# S7G7_footprint_simplified_w_ethernet_v1p.net
KiCad netlist of a schematic drawn in EAGLE
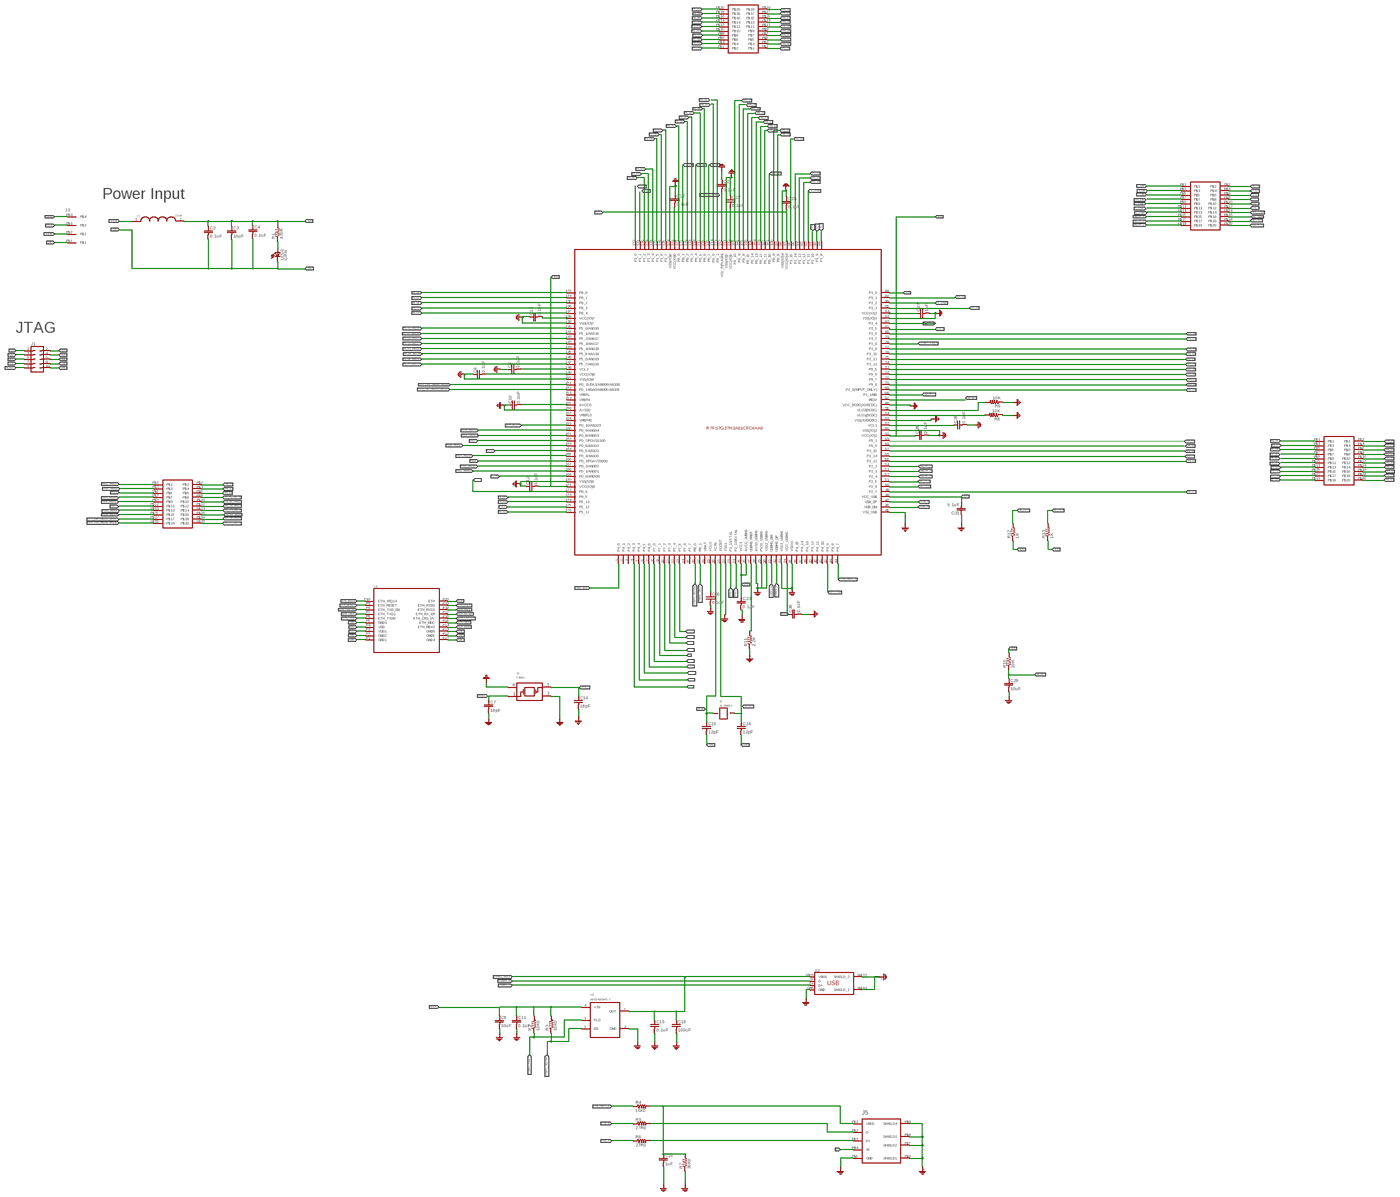
[diagram p0: schematic, sheet 1, overview]
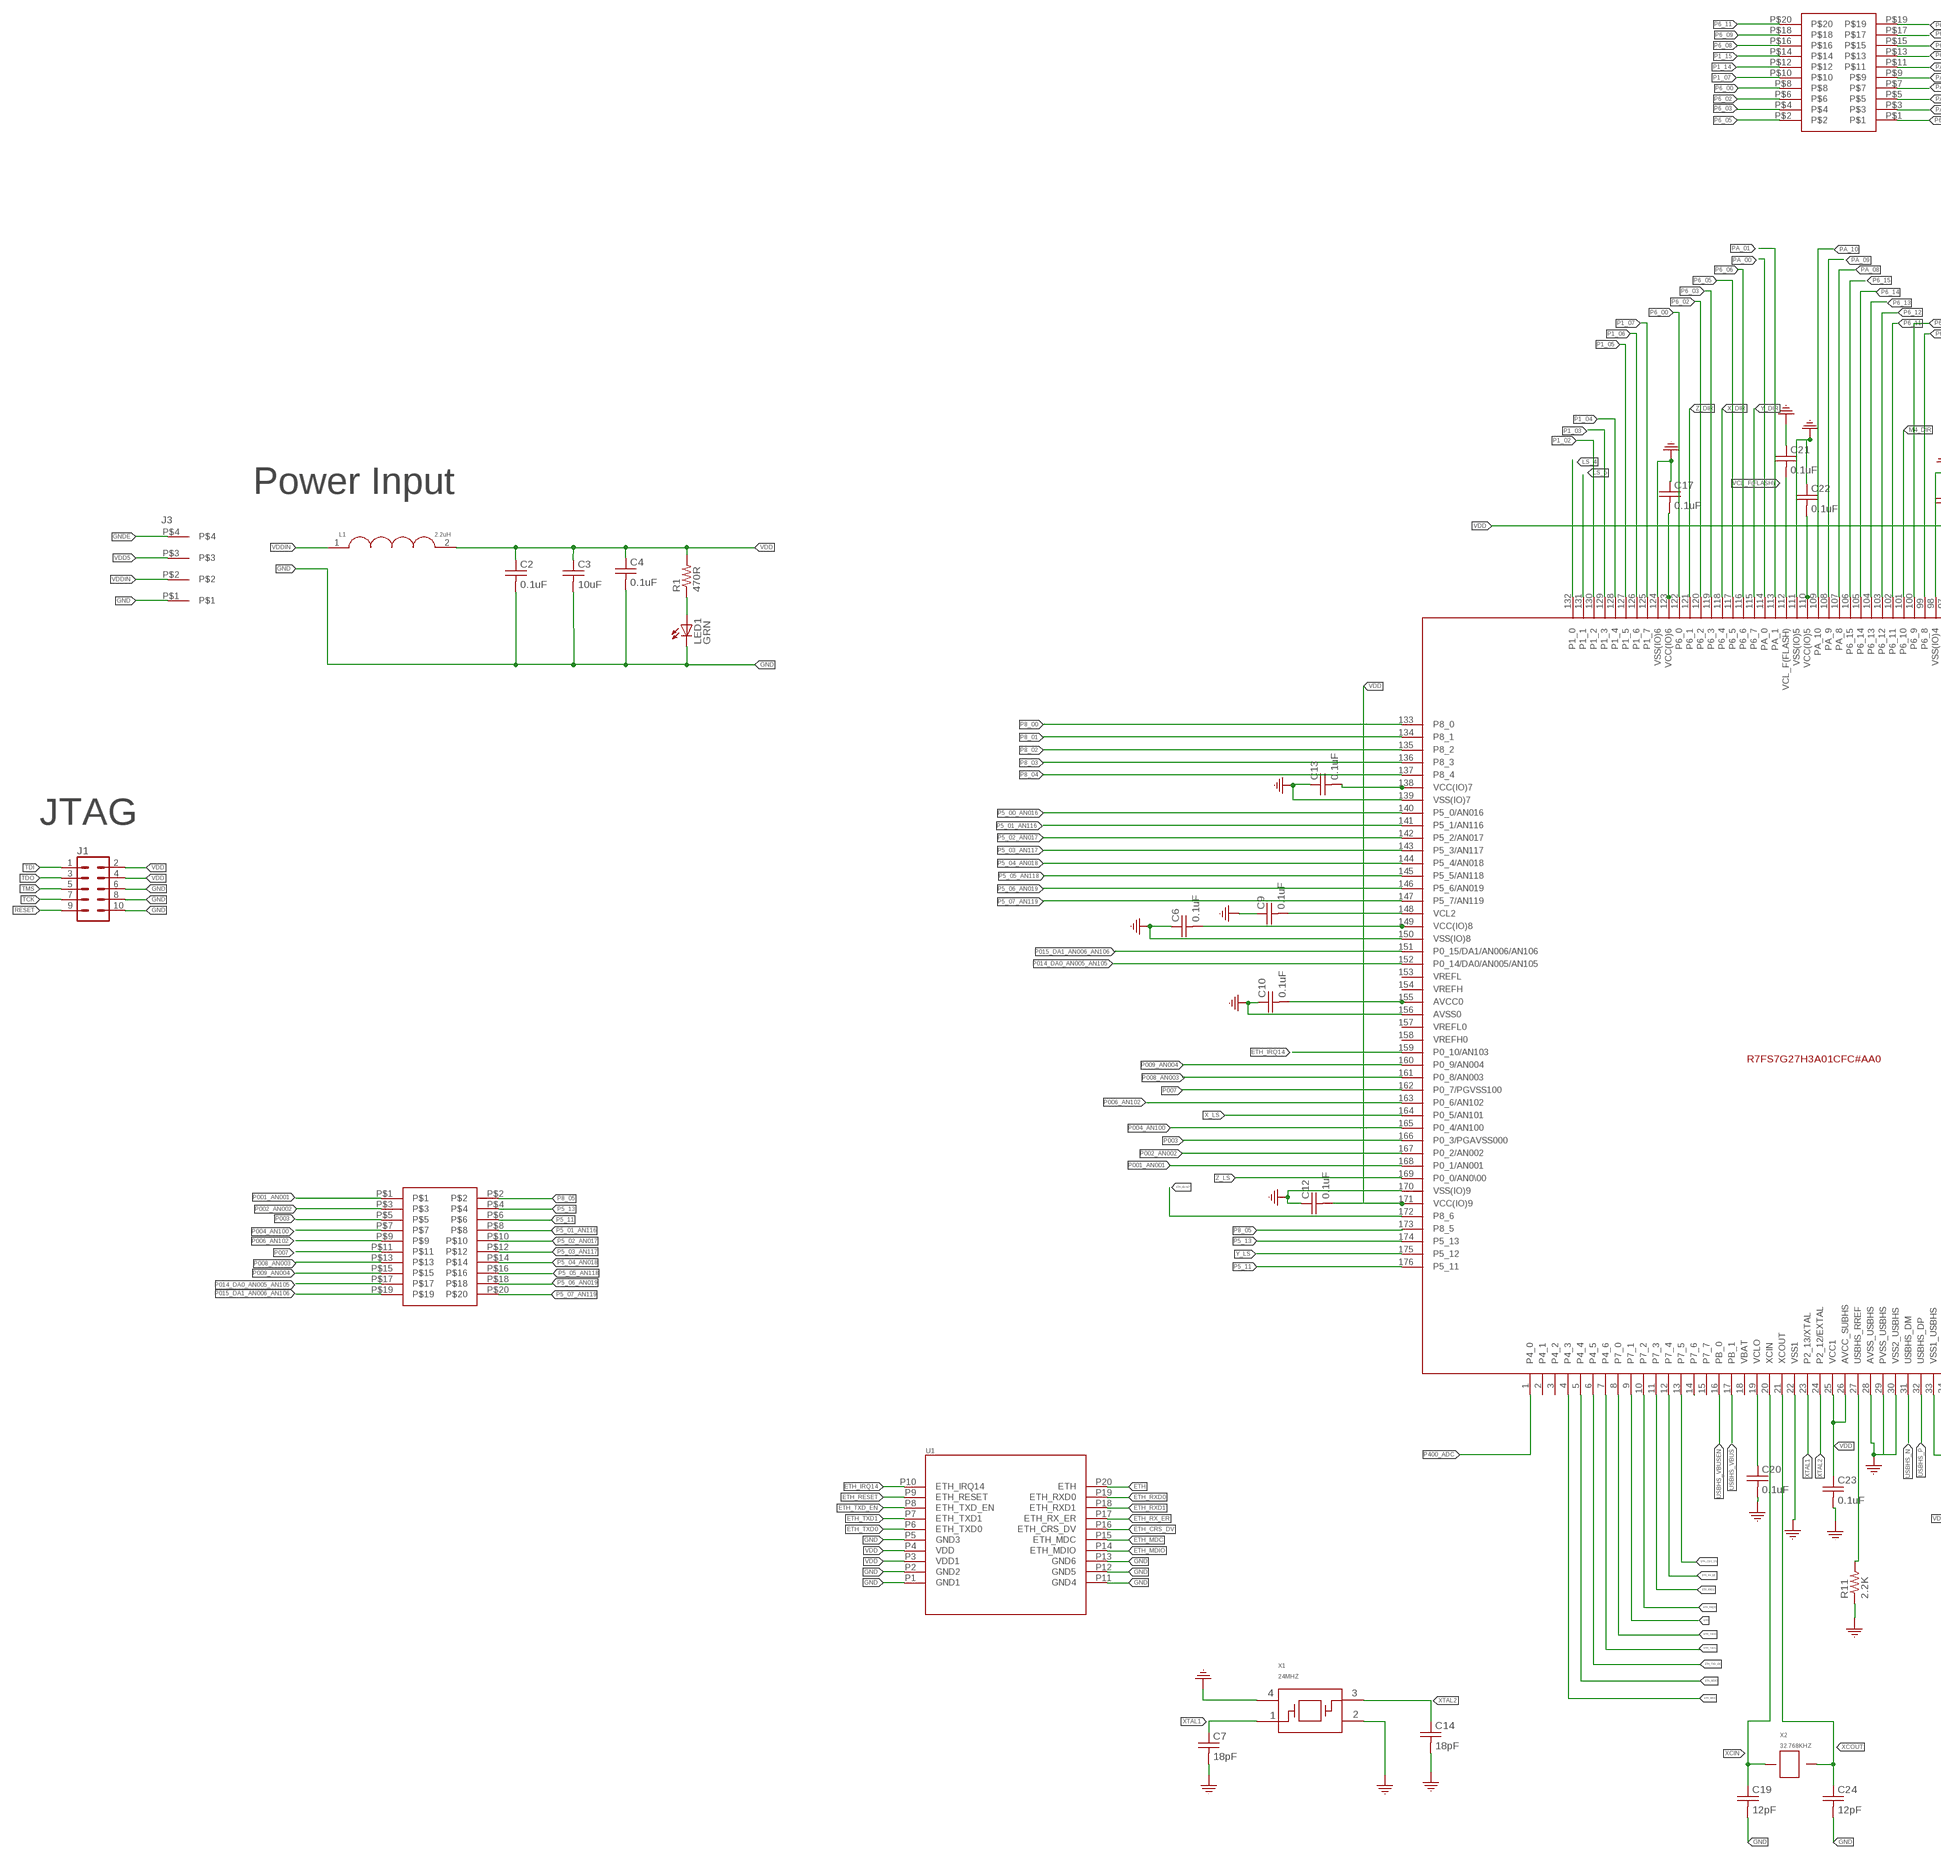
[diagram p1: schematic, sheet 1, part 1 of 4]
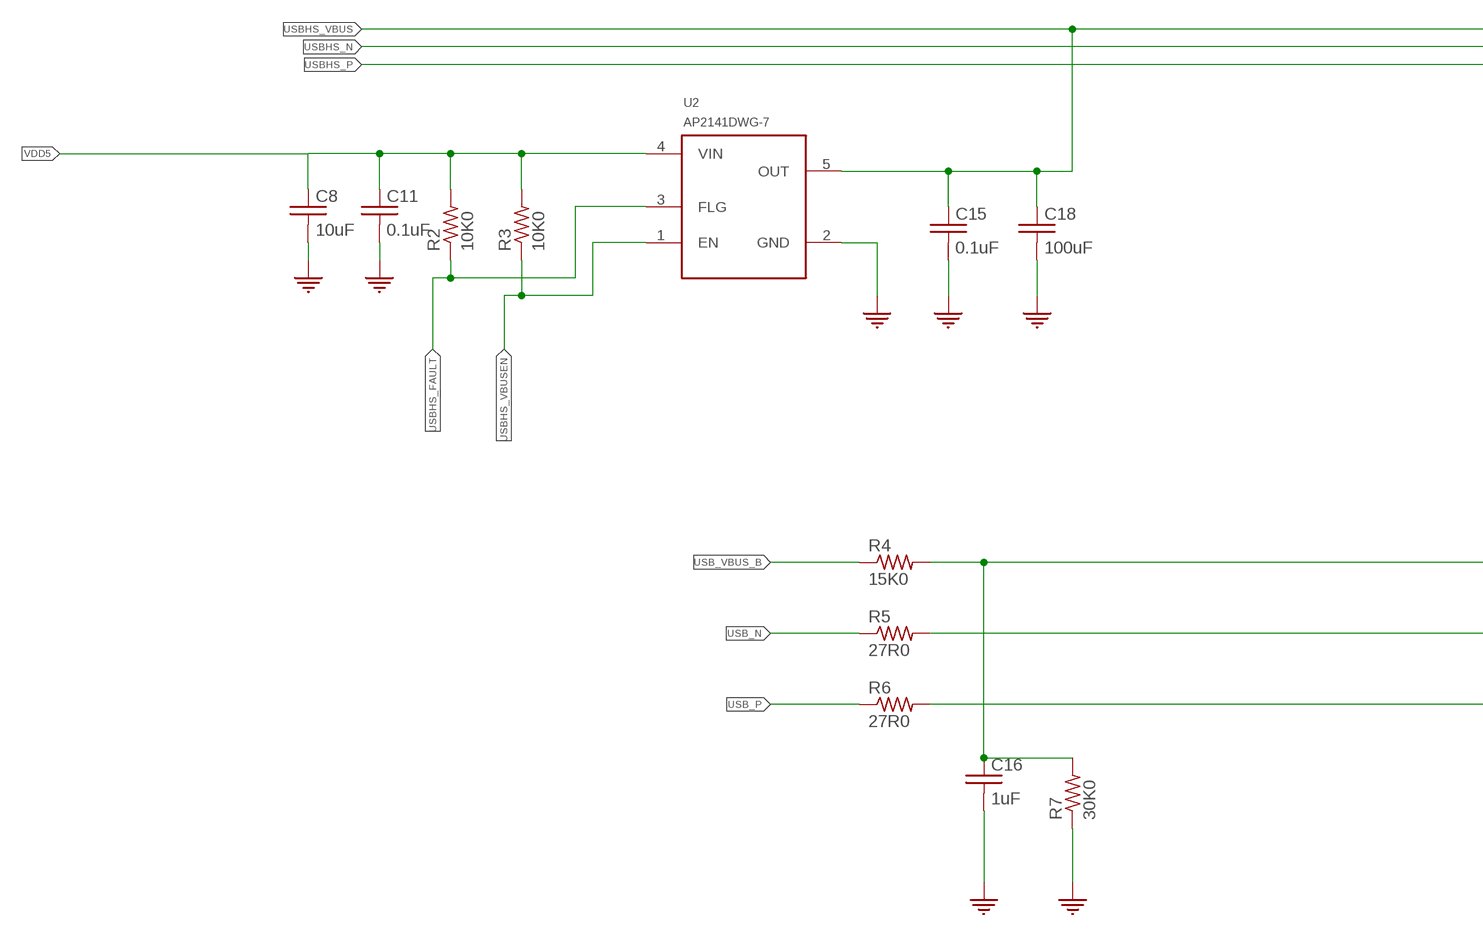
[diagram p2: schematic, sheet 1, part 2 of 4]
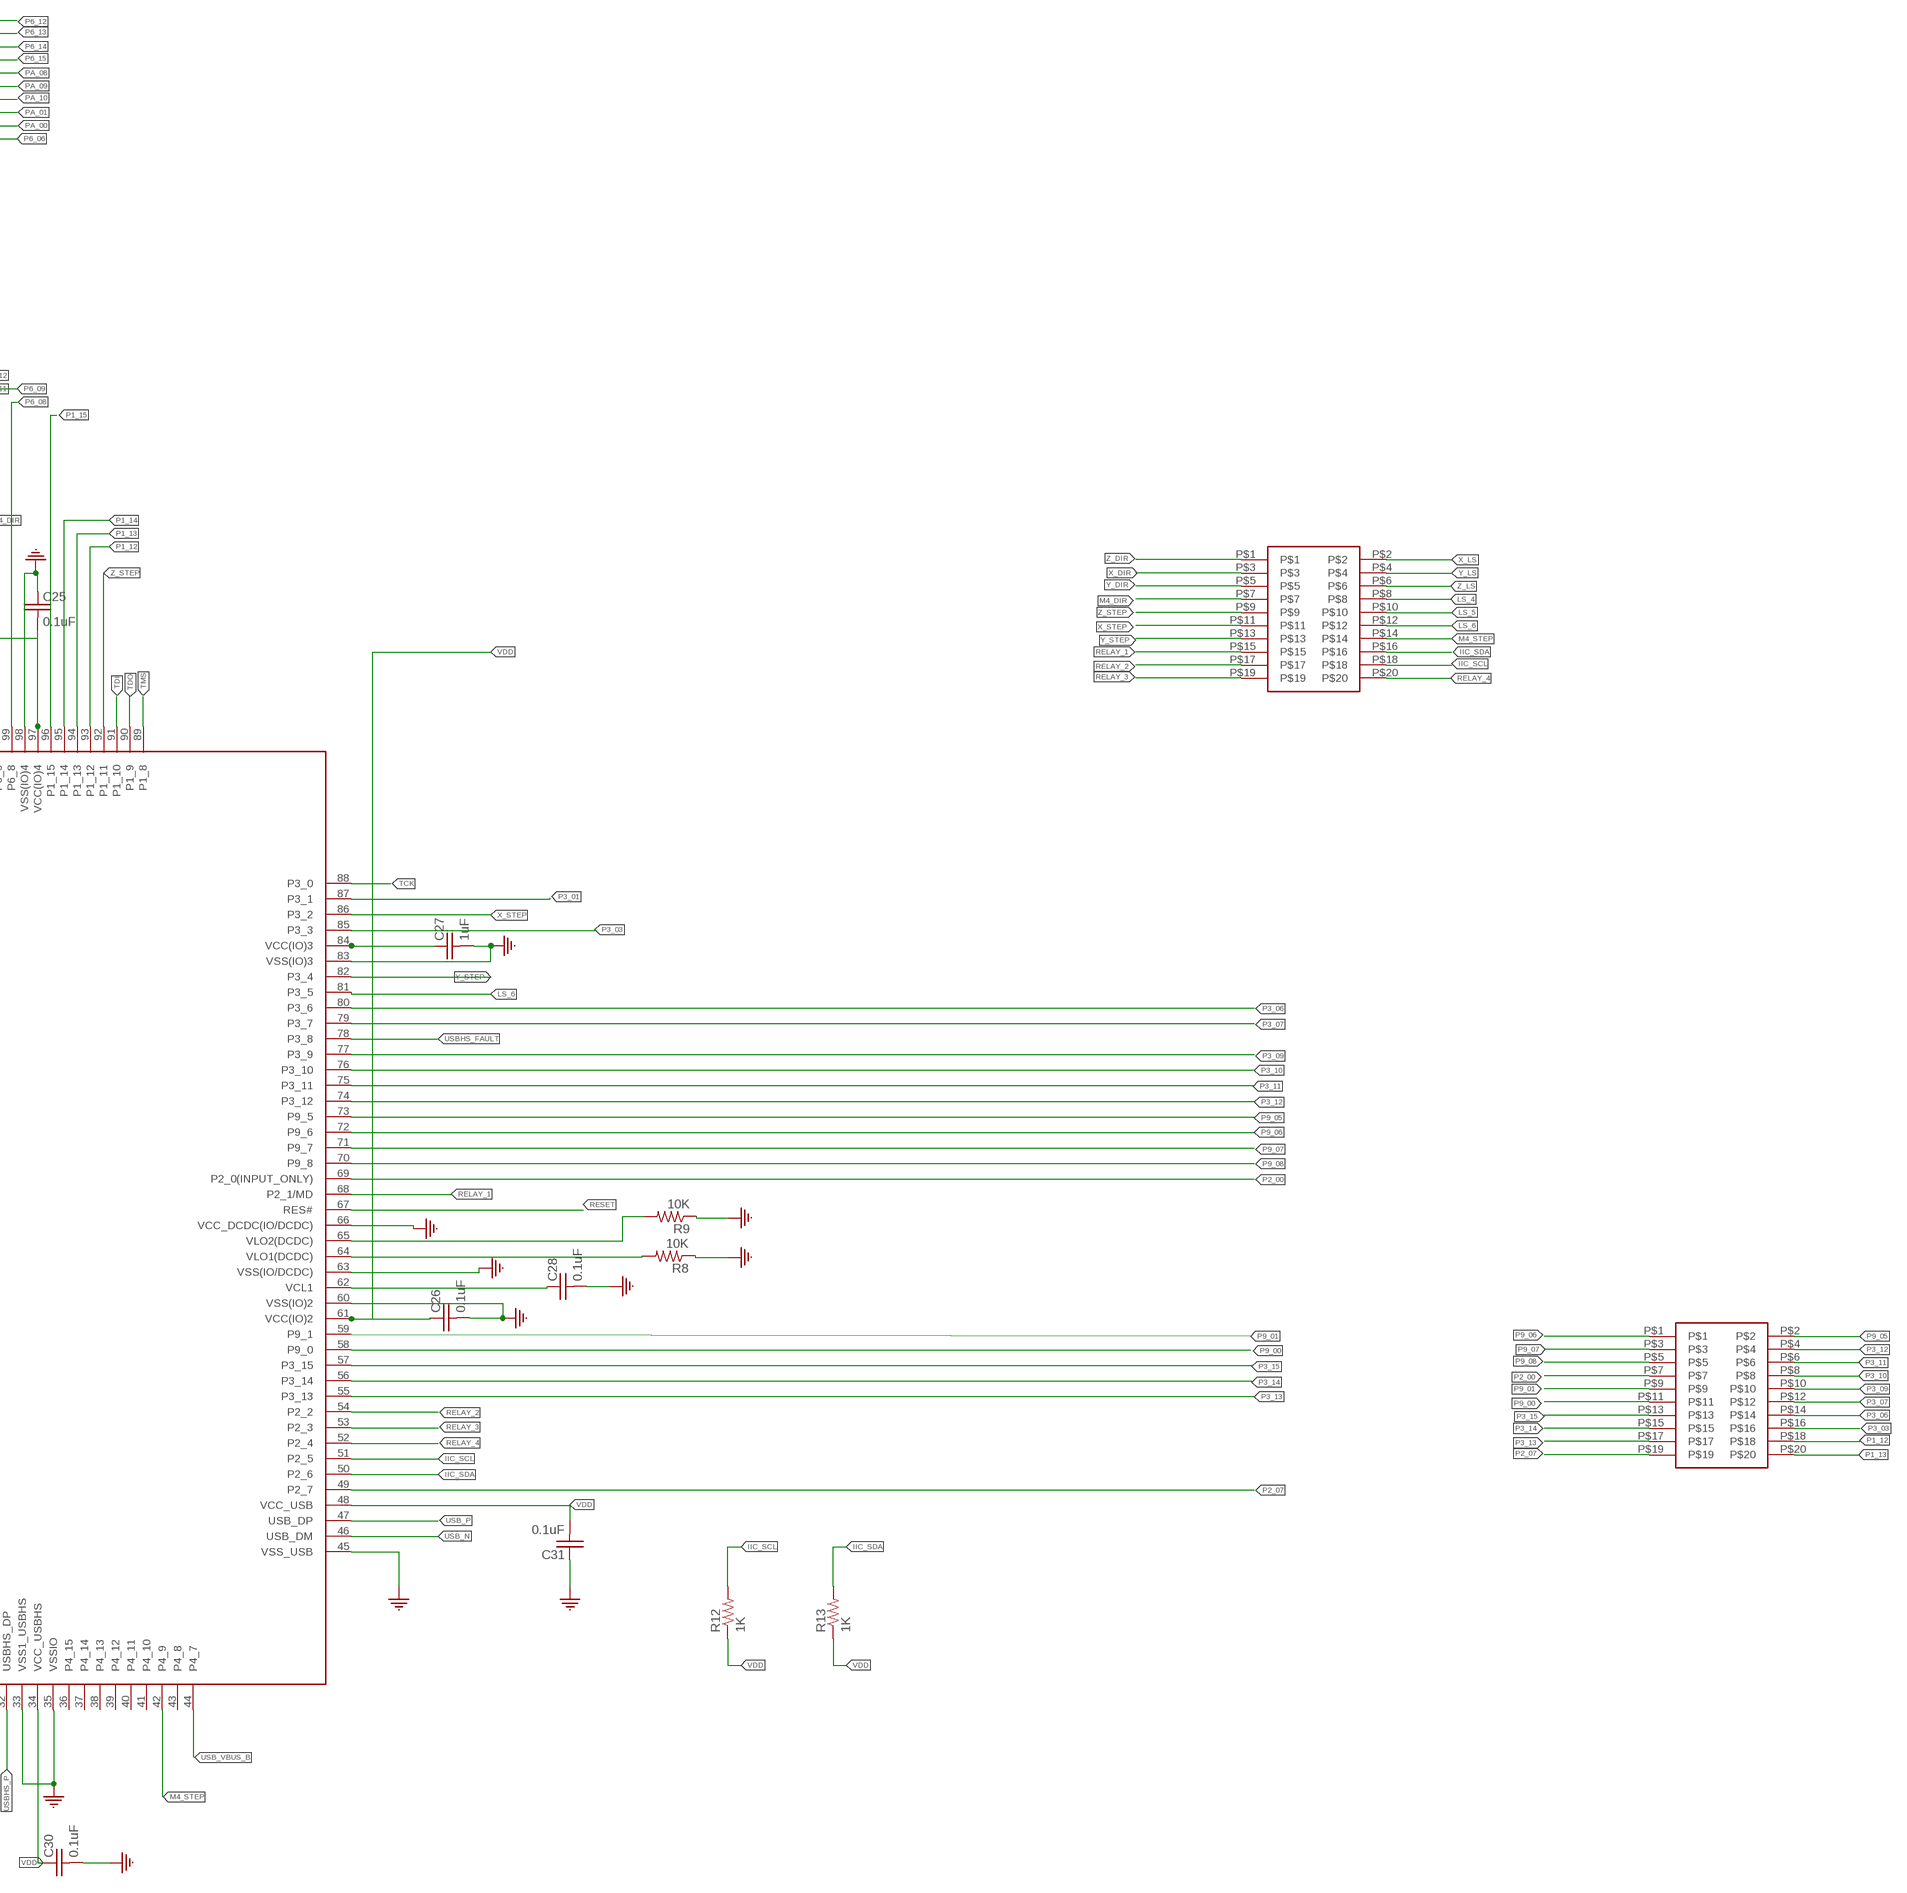
[diagram p3: schematic, sheet 1, part 3 of 4]
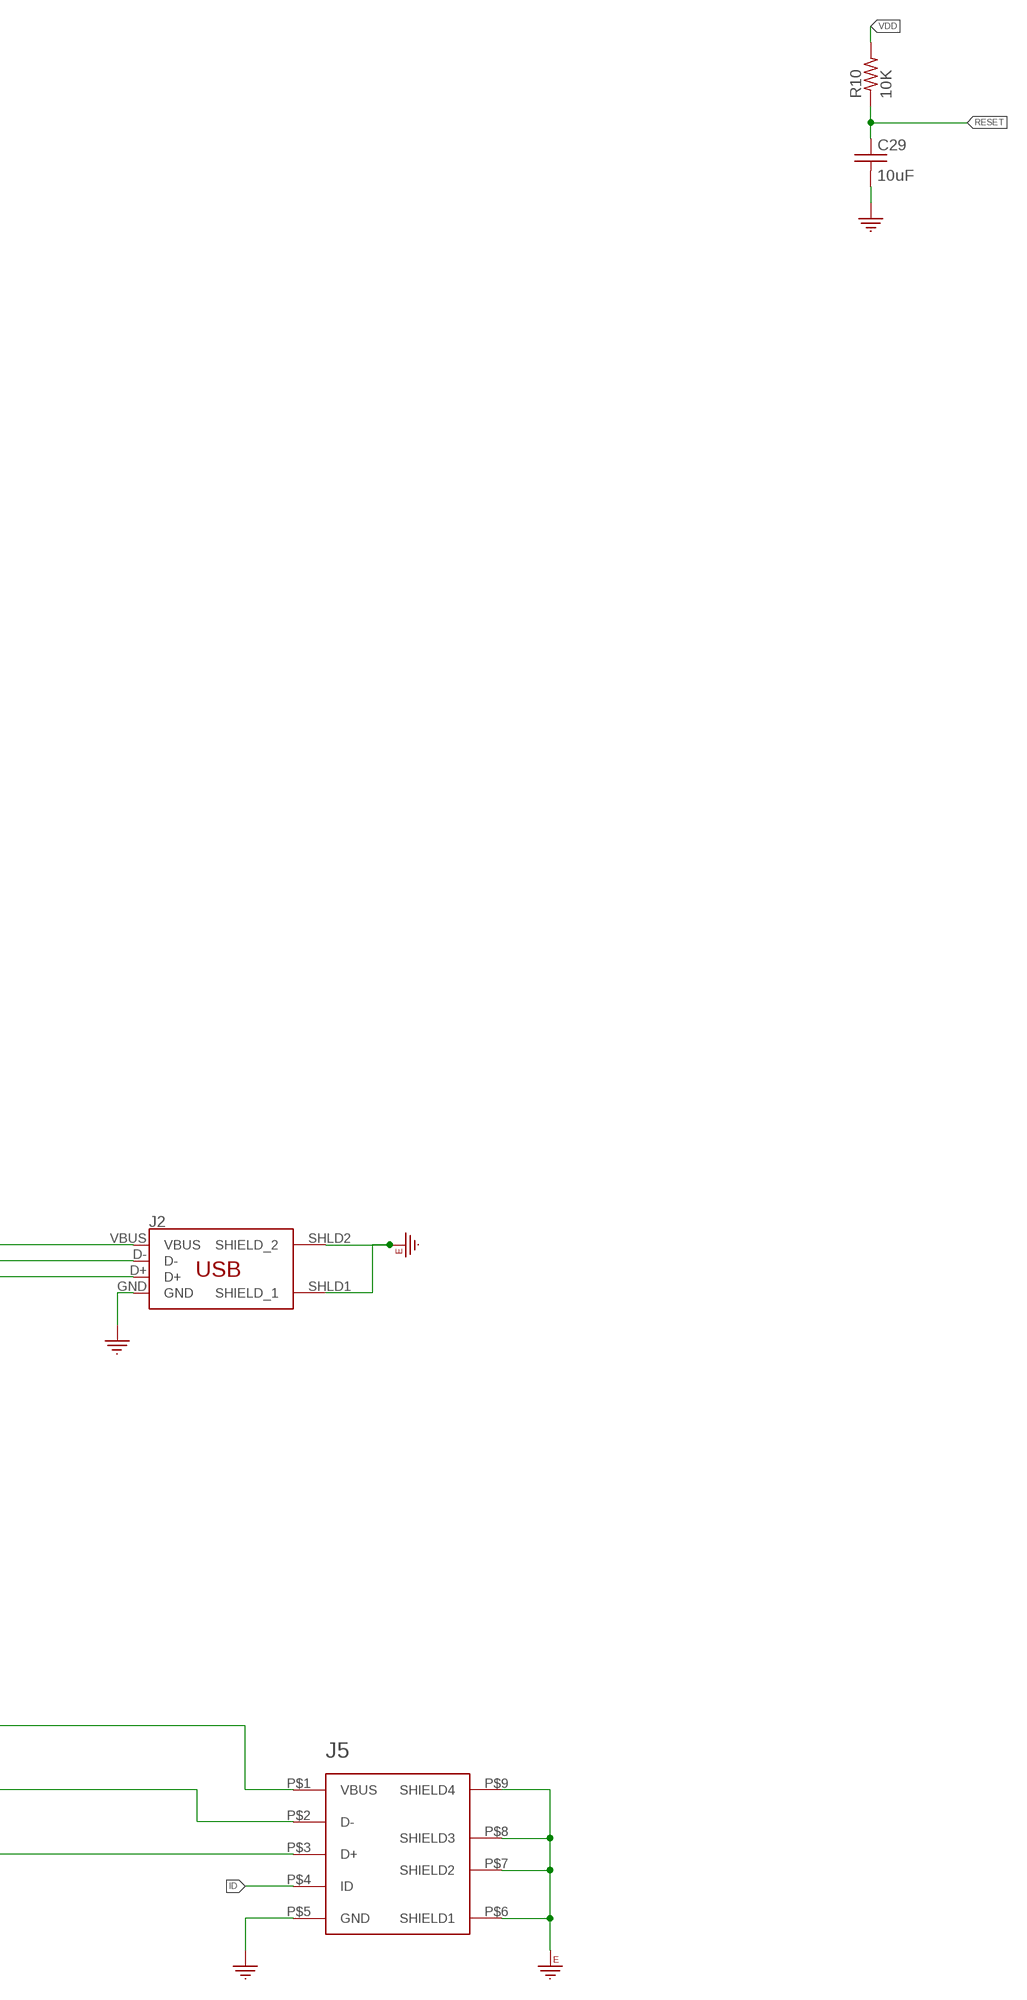
[diagram p4: schematic, sheet 1, part 4 of 4]

(export (version "E")
  (design (tool "Eeschema 10.0.6"))
  (components
    (comp (ref "C2")
      (value "0.1uF")
      (footprint "eagle-import:0402")
      (libsource (lib "eagle-import") (part "C_0402"))
    )
    (comp (ref "C3")
      (value "10uF")
      (footprint "eagle-import:0402")
      (libsource (lib "eagle-import") (part "C_0402"))
    )
    (comp (ref "C4")
      (value "0.1uF")
      (footprint "eagle-import:0402")
      (libsource (lib "eagle-import") (part "C_0402"))
    )
    (comp (ref "C6")
      (value "0.1uF")
      (footprint "eagle-import:0402")
      (libsource (lib "eagle-import") (part "C_0402"))
    )
    (comp (ref "C7")
      (value "18pF")
      (footprint "eagle-import:0402")
      (libsource (lib "eagle-import") (part "C_0402"))
    )
    (comp (ref "C8")
      (value "10uF")
      (footprint "eagle-import:0402")
      (libsource (lib "eagle-import") (part "C_0402"))
    )
    (comp (ref "C9")
      (value "0.1uF")
      (footprint "eagle-import:0402")
      (libsource (lib "eagle-import") (part "C_0402"))
    )
    (comp (ref "C10")
      (value "0.1uF")
      (footprint "eagle-import:0402")
      (libsource (lib "eagle-import") (part "C_0402"))
    )
    (comp (ref "C11")
      (value "0.1uF")
      (footprint "eagle-import:0402")
      (libsource (lib "eagle-import") (part "C_0402"))
    )
    (comp (ref "C12")
      (value "0.1uF")
      (footprint "eagle-import:0402")
      (libsource (lib "eagle-import") (part "C_0402"))
    )
    (comp (ref "C13")
      (value "0.1uF")
      (footprint "eagle-import:0402")
      (libsource (lib "eagle-import") (part "C_0402"))
    )
    (comp (ref "C14")
      (value "18pF")
      (footprint "eagle-import:0402")
      (libsource (lib "eagle-import") (part "C_0402"))
    )
    (comp (ref "C15")
      (value "0.1uF")
      (footprint "eagle-import:0402")
      (libsource (lib "eagle-import") (part "C_0402"))
    )
    (comp (ref "C16")
      (value "1uF")
      (footprint "eagle-import:0402")
      (libsource (lib "eagle-import") (part "C_0402"))
    )
    (comp (ref "C17")
      (value "0.1uF")
      (footprint "eagle-import:0402")
      (libsource (lib "eagle-import") (part "C_0402"))
    )
    (comp (ref "C18")
      (value "100uF")
      (footprint "eagle-import:C1210")
      (libsource (lib "eagle-import") (part "C_1210"))
    )
    (comp (ref "C19")
      (value "12pF")
      (footprint "eagle-import:0402")
      (libsource (lib "eagle-import") (part "C_0402"))
    )
    (comp (ref "C20")
      (value "0.1uF")
      (footprint "eagle-import:0402")
      (libsource (lib "eagle-import") (part "C_0402"))
    )
    (comp (ref "C21")
      (value "0.1uF")
      (footprint "eagle-import:0402")
      (libsource (lib "eagle-import") (part "C_0402"))
    )
    (comp (ref "C22")
      (value "0.1uF")
      (footprint "eagle-import:0402")
      (libsource (lib "eagle-import") (part "C_0402"))
    )
    (comp (ref "C23")
      (value "0.1uF")
      (footprint "eagle-import:0402")
      (libsource (lib "eagle-import") (part "C_0402"))
    )
    (comp (ref "C24")
      (value "12pF")
      (footprint "eagle-import:0402")
      (libsource (lib "eagle-import") (part "C_0402"))
    )
    (comp (ref "C25")
      (value "0.1uF")
      (footprint "eagle-import:0402")
      (libsource (lib "eagle-import") (part "C_0402"))
    )
    (comp (ref "C26")
      (value "0.1uF")
      (footprint "eagle-import:0402")
      (libsource (lib "eagle-import") (part "C_0402"))
    )
    (comp (ref "C27")
      (value "1uF")
      (footprint "eagle-import:0402")
      (libsource (lib "eagle-import") (part "C_0402"))
    )
    (comp (ref "C28")
      (value "0.1uF")
      (footprint "eagle-import:0402")
      (libsource (lib "eagle-import") (part "C_0402"))
    )
    (comp (ref "C29")
      (value "10uF")
      (footprint "eagle-import:0402")
      (libsource (lib "eagle-import") (part "C_0402"))
    )
    (comp (ref "C30")
      (value "0.1uF")
      (footprint "eagle-import:0402")
      (libsource (lib "eagle-import") (part "C_0402"))
    )
    (comp (ref "C31")
      (value "0.1uF")
      (footprint "eagle-import:0402")
      (libsource (lib "eagle-import") (part "C_0402"))
    )
    (comp (ref "J1")
      (value "CONN_05X2PTH")
      (footprint "eagle-import:2X5")
      (libsource (lib "eagle-import") (part "CONN_05X2PTH"))
    )
    (comp (ref "J2")
      (value "USB_A")
      (footprint "eagle-import:USB_A_SMT")
      (libsource (lib "eagle-import") (part "USB_A"))
    )
    (comp (ref "J3")
      (value "3.81MM_1_X_4_RT_ANGLE_PLUG_HEADER")
      (footprint "eagle-import:1X4_3.81MM_PITCH")
      (libsource (lib "eagle-import") (part "3.81MM_1_X_4_RT_ANGLE_PLUG_HEADER"))
    )
    (comp (ref "J4")
      (value "2_X_10_HEADER_GENERIC")
      (footprint "eagle-import:2_X_10_.1_INCH")
      (libsource (lib "eagle-import") (part "2_X_10_HEADER_GENERIC"))
    )
    (comp (ref "J5")
      (value "USB_MICRO-B")
      (footprint "eagle-import:USB_MICRO-B")
      (libsource (lib "eagle-import") (part "USB_MICRO-B"))
    )
    (comp (ref "JP1")
      (value "2_X_10_HEADER_GENERIC")
      (footprint "eagle-import:2_X_10_.1_INCH")
      (libsource (lib "eagle-import") (part "2_X_10_HEADER_GENERIC"))
    )
    (comp (ref "JP2")
      (value "2_X_10_HEADER_GENERIC")
      (footprint "eagle-import:2_X_10_.1_INCH")
      (libsource (lib "eagle-import") (part "2_X_10_HEADER_GENERIC"))
    )
    (comp (ref "JP3")
      (value "2_X_10_HEADER_GENERIC")
      (footprint "eagle-import:2_X_10_.1_INCH")
      (libsource (lib "eagle-import") (part "2_X_10_HEADER_GENERIC"))
    )
    (comp (ref "L1")
      (value "2.2uH")
      (footprint "eagle-import:1008_(2520_METRIC)")
      (libsource (lib "eagle-import") (part "INDUCTOR_1008_2.2_MH_1.3A"))
    )
    (comp (ref "LED1")
      (value "LED_0805_GREEN")
      (footprint "eagle-import:LED_0805_GREEN")
      (libsource (lib "eagle-import") (part "LED_0805_GREEN"))
    )
    (comp (ref "R1")
      (value "470R")
      (footprint "eagle-import:0402")
      (libsource (lib "eagle-import") (part "R_0402"))
    )
    (comp (ref "R2")
      (value "10K0")
      (footprint "eagle-import:0402")
      (libsource (lib "eagle-import") (part "R_0402"))
    )
    (comp (ref "R3")
      (value "10K0")
      (footprint "eagle-import:0402")
      (libsource (lib "eagle-import") (part "R_0402"))
    )
    (comp (ref "R4")
      (value "15K0")
      (footprint "eagle-import:0402")
      (libsource (lib "eagle-import") (part "R_0402"))
    )
    (comp (ref "R5")
      (value "27R0")
      (footprint "eagle-import:0402")
      (libsource (lib "eagle-import") (part "R_0402"))
    )
    (comp (ref "R6")
      (value "27R0")
      (footprint "eagle-import:0402")
      (libsource (lib "eagle-import") (part "R_0402"))
    )
    (comp (ref "R7")
      (value "30K0")
      (footprint "eagle-import:0402")
      (libsource (lib "eagle-import") (part "R_0402"))
    )
    (comp (ref "R8")
      (value "10K")
      (footprint "eagle-import:0402")
      (libsource (lib "eagle-import") (part "R_0402"))
    )
    (comp (ref "R9")
      (value "10K")
      (footprint "eagle-import:0402")
      (libsource (lib "eagle-import") (part "R_0402"))
    )
    (comp (ref "R10")
      (value "10K")
      (footprint "eagle-import:0402")
      (libsource (lib "eagle-import") (part "R_0402"))
    )
    (comp (ref "R11")
      (value "2.2K")
      (footprint "eagle-import:0402")
      (libsource (lib "eagle-import") (part "R_0402"))
    )
    (comp (ref "R12")
      (value "1K")
      (footprint "eagle-import:0402")
      (libsource (lib "eagle-import") (part "R_0402"))
    )
    (comp (ref "R13")
      (value "1K")
      (footprint "eagle-import:0402")
      (libsource (lib "eagle-import") (part "R_0402"))
    )
    (comp (ref "U1")
      (value "ETHERNET_HAT")
      (footprint "eagle-import:ETHERNET_HAT")
      (libsource (lib "eagle-import") (part "ETHERNET_HAT"))
    )
    (comp (ref "U2")
      (value "AP2141DWG-5")
      (footprint "eagle-import:SOT-23-5")
      (libsource (lib "eagle-import") (part "AP2141DWG-5"))
    )
    (comp (ref "U5")
      (value "S7G2_X_176")
      (footprint "eagle-import:LQFP176_24X24")
      (libsource (lib "eagle-import") (part "S7G2_X_176"))
    )
    (comp (ref "X1")
      (value "24MHZ")
      (footprint "eagle-import:SMD_3225")
      (libsource (lib "eagle-import") (part "XTAL_24_MHZ"))
    )
    (comp (ref "X2")
      (value "32.768KHZ")
      (footprint "eagle-import:SMD_X_2_PADS")
      (libsource (lib "eagle-import") (part "XTAL_32.768KHZ"))
    )
  )
  (nets
    (net (code "1") (name "ETH") (class "Default")
      (node (ref "U1") (pin "P20") (pinfunction "ETH_P20") (pintype "bidirectional"))
      (node (ref "U5") (pin "9") (pinfunction "P7_1_9") (pintype "bidirectional"))
    )
    (net (code "2") (name "ETH_CRS_DV") (class "Default")
      (node (ref "U1") (pin "P16") (pinfunction "ETH_CRS_DV_P16") (pintype "bidirectional"))
      (node (ref "U5") (pin "13") (pinfunction "P7_5_13") (pintype "bidirectional"))
    )
    (net (code "3") (name "ETH_IRQ14") (class "Default")
      (node (ref "U1") (pin "P10") (pinfunction "ETH_IRQ14_P10") (pintype "bidirectional"))
      (node (ref "U5") (pin "159") (pinfunction "P0_10/AN103_159") (pintype "bidirectional"))
    )
    (net (code "4") (name "ETH_MDC") (class "Default")
      (node (ref "U1") (pin "P15") (pinfunction "ETH_MDC_P15") (pintype "bidirectional"))
      (node (ref "U5") (pin "4") (pinfunction "P4_3_4") (pintype "bidirectional"))
    )
    (net (code "5") (name "ETH_MDIO") (class "Default")
      (node (ref "U1") (pin "P14") (pinfunction "ETH_MDIO_P14") (pintype "bidirectional"))
      (node (ref "U5") (pin "5") (pinfunction "P4_4_5") (pintype "bidirectional"))
    )
    (net (code "6") (name "ETH_RESET") (class "Default")
      (node (ref "U1") (pin "P9") (pinfunction "ETH_RESET_P9") (pintype "bidirectional"))
      (node (ref "U5") (pin "172") (pinfunction "P8_6_172") (pintype "bidirectional"))
    )
    (net (code "7") (name "ETH_RXD0") (class "Default")
      (node (ref "U1") (pin "P19") (pinfunction "ETH_RXD0_P19") (pintype "bidirectional"))
      (node (ref "U5") (pin "10") (pinfunction "P7_2_10") (pintype "bidirectional"))
    )
    (net (code "8") (name "ETH_RXD1") (class "Default")
      (node (ref "U1") (pin "P18") (pinfunction "ETH_RXD1_P18") (pintype "bidirectional"))
      (node (ref "U5") (pin "11") (pinfunction "P7_3_11") (pintype "bidirectional"))
    )
    (net (code "9") (name "ETH_RX_ER") (class "Default")
      (node (ref "U1") (pin "P17") (pinfunction "ETH_RX_ER_P17") (pintype "bidirectional"))
      (node (ref "U5") (pin "12") (pinfunction "P7_4_12") (pintype "bidirectional"))
    )
    (net (code "10") (name "ETH_TXD0") (class "Default")
      (node (ref "U1") (pin "P6") (pinfunction "ETH_TXD0_P6") (pintype "bidirectional"))
      (node (ref "U5") (pin "8") (pinfunction "P7_0_8") (pintype "bidirectional"))
    )
    (net (code "11") (name "ETH_TXD1") (class "Default")
      (node (ref "U1") (pin "P7") (pinfunction "ETH_TXD1_P7") (pintype "bidirectional"))
      (node (ref "U5") (pin "7") (pinfunction "P4_6_7") (pintype "bidirectional"))
    )
    (net (code "12") (name "ETH_TXD_EN") (class "Default")
      (node (ref "U1") (pin "P8") (pinfunction "ETH_TXD_EN_P8") (pintype "bidirectional"))
      (node (ref "U5") (pin "6") (pinfunction "P4_5_6") (pintype "bidirectional"))
    )
    (net (code "13") (name "GND") (class "Default")
      (node (ref "C10") (pin "P$1") (pinfunction "1_P$1") (pintype "passive"))
      (node (ref "C11") (pin "P$2") (pinfunction "2_P$2") (pintype "passive"))
      (node (ref "C12") (pin "P$1") (pinfunction "1_P$1") (pintype "passive"))
      (node (ref "C13") (pin "P$1") (pinfunction "1_P$1") (pintype "passive"))
      (node (ref "C14") (pin "P$2") (pinfunction "2_P$2") (pintype "passive"))
      (node (ref "C15") (pin "P$2") (pinfunction "2_P$2") (pintype "passive"))
      (node (ref "C16") (pin "P$2") (pinfunction "2_P$2") (pintype "passive"))
      (node (ref "C17") (pin "P$1") (pinfunction "1_P$1") (pintype "passive"))
      (node (ref "C18") (pin "2") (pinfunction "2_2") (pintype "passive"))
      (node (ref "C19") (pin "P$2") (pinfunction "2_P$2") (pintype "passive"))
      (node (ref "C2") (pin "P$2") (pinfunction "2_P$2") (pintype "passive"))
      (node (ref "C20") (pin "P$2") (pinfunction "2_P$2") (pintype "passive"))
      (node (ref "C21") (pin "P$1") (pinfunction "1_P$1") (pintype "passive"))
      (node (ref "C22") (pin "P$1") (pinfunction "1_P$1") (pintype "passive"))
      (node (ref "C23") (pin "P$2") (pinfunction "2_P$2") (pintype "passive"))
      (node (ref "C24") (pin "P$2") (pinfunction "2_P$2") (pintype "passive"))
      (node (ref "C25") (pin "P$1") (pinfunction "1_P$1") (pintype "passive"))
      (node (ref "C26") (pin "P$2") (pinfunction "2_P$2") (pintype "passive"))
      (node (ref "C27") (pin "P$2") (pinfunction "2_P$2") (pintype "passive"))
      (node (ref "C28") (pin "P$2") (pinfunction "2_P$2") (pintype "passive"))
      (node (ref "C29") (pin "P$2") (pinfunction "2_P$2") (pintype "passive"))
      (node (ref "C3") (pin "P$2") (pinfunction "2_P$2") (pintype "passive"))
      (node (ref "C30") (pin "P$2") (pinfunction "2_P$2") (pintype "passive"))
      (node (ref "C31") (pin "P$1") (pinfunction "1_P$1") (pintype "passive"))
      (node (ref "C4") (pin "P$2") (pinfunction "2_P$2") (pintype "passive"))
      (node (ref "C6") (pin "P$1") (pinfunction "1_P$1") (pintype "passive"))
      (node (ref "C7") (pin "P$2") (pinfunction "2_P$2") (pintype "passive"))
      (node (ref "C8") (pin "P$2") (pinfunction "2_P$2") (pintype "passive"))
      (node (ref "C9") (pin "P$1") (pinfunction "1_P$1") (pintype "passive"))
      (node (ref "J1") (pin "10") (pinfunction "10_10") (pintype "passive"))
      (node (ref "J1") (pin "6") (pinfunction "6_6") (pintype "passive"))
      (node (ref "J1") (pin "8") (pinfunction "8_8") (pintype "passive"))
      (node (ref "J2") (pin "GND") (pinfunction "GND_GND") (pintype "power_in"))
      (node (ref "J3") (pin "P$1") (pinfunction "P$1_P$1") (pintype "bidirectional"))
      (node (ref "J5") (pin "P$5") (pinfunction "GND_P$5") (pintype "bidirectional"))
      (node (ref "LED1") (pin "C") (pinfunction "C_C") (pintype "passive"))
      (node (ref "R11") (pin "P$1") (pinfunction "1_P$1") (pintype "passive"))
      (node (ref "R7") (pin "P$1") (pinfunction "1_P$1") (pintype "passive"))
      (node (ref "R8") (pin "P$1") (pinfunction "1_P$1") (pintype "passive"))
      (node (ref "R9") (pin "P$1") (pinfunction "1_P$1") (pintype "passive"))
      (node (ref "U1") (pin "P1") (pinfunction "GND1_P1") (pintype "bidirectional"))
      (node (ref "U1") (pin "P11") (pinfunction "GND4_P11") (pintype "bidirectional"))
      (node (ref "U1") (pin "P12") (pinfunction "GND5_P12") (pintype "bidirectional"))
      (node (ref "U1") (pin "P13") (pinfunction "GND6_P13") (pintype "bidirectional"))
      (node (ref "U1") (pin "P2") (pinfunction "GND2_P2") (pintype "bidirectional"))
      (node (ref "U1") (pin "P5") (pinfunction "GND3_P5") (pintype "bidirectional"))
      (node (ref "U2") (pin "2") (pinfunction "GND_2") (pintype "input"))
      (node (ref "U5") (pin "111") (pinfunction "VSS(IO)5_111") (pintype "bidirectional"))
      (node (ref "U5") (pin "124") (pinfunction "VSS(IO)6_124") (pintype "bidirectional"))
      (node (ref "U5") (pin "139") (pinfunction "VSS(IO)7_139") (pintype "bidirectional"))
      (node (ref "U5") (pin "150") (pinfunction "VSS(IO)8_150") (pintype "bidirectional"))
      (node (ref "U5") (pin "156") (pinfunction "AVSS0_156") (pintype "bidirectional"))
      (node (ref "U5") (pin "170") (pinfunction "VSS(IO)9_170") (pintype "bidirectional"))
      (node (ref "U5") (pin "22") (pinfunction "VSS1_22") (pintype "bidirectional"))
      (node (ref "U5") (pin "28") (pinfunction "AVSS_USBHS_28") (pintype "bidirectional"))
      (node (ref "U5") (pin "29") (pinfunction "PVSS_USBHS_29") (pintype "bidirectional"))
      (node (ref "U5") (pin "30") (pinfunction "VSS2_USBHS_30") (pintype "bidirectional"))
      (node (ref "U5") (pin "33") (pinfunction "VSS1_USBHS_33") (pintype "bidirectional"))
      (node (ref "U5") (pin "35") (pinfunction "VSSIO_35") (pintype "bidirectional"))
      (node (ref "U5") (pin "45") (pinfunction "VSS_USB_45") (pintype "bidirectional"))
      (node (ref "U5") (pin "60") (pinfunction "VSS(IO)2_60") (pintype "bidirectional"))
      (node (ref "U5") (pin "63") (pinfunction "VSS(IO/DCDC)_63") (pintype "bidirectional"))
      (node (ref "U5") (pin "66") (pinfunction "VCC_DCDC(IO/DCDC)_66") (pintype "bidirectional"))
      (node (ref "U5") (pin "83") (pinfunction "VSS(IO)3_83") (pintype "bidirectional"))
      (node (ref "U5") (pin "98") (pinfunction "VSS(IO)4_98") (pintype "bidirectional"))
      (node (ref "X1") (pin "2") (pinfunction "2_2") (pintype "bidirectional"))
      (node (ref "X1") (pin "4") (pinfunction "4_4") (pintype "bidirectional"))
    )
    (net (code "14") (name "GNDE") (class "Default")
      (node (ref "J2") (pin "SHLD1") (pinfunction "SHIELD_1_SHLD1") (pintype "bidirectional"))
      (node (ref "J2") (pin "SHLD2") (pinfunction "SHIELD_2_SHLD2") (pintype "bidirectional"))
      (node (ref "J3") (pin "P$4") (pinfunction "P$4_P$4") (pintype "bidirectional"))
      (node (ref "J5") (pin "P$6") (pinfunction "SHIELD1_P$6") (pintype "bidirectional"))
      (node (ref "J5") (pin "P$7") (pinfunction "SHIELD2_P$7") (pintype "bidirectional"))
      (node (ref "J5") (pin "P$8") (pinfunction "SHIELD3_P$8") (pintype "bidirectional"))
      (node (ref "J5") (pin "P$9") (pinfunction "SHIELD4_P$9") (pintype "bidirectional"))
    )
    (net (code "15") (name "ID") (class "Default")
      (node (ref "J5") (pin "P$4") (pinfunction "ID_P$4") (pintype "bidirectional"))
    )
    (net (code "16") (name "IIC_SCL") (class "Default")
      (node (ref "J4") (pin "P$18") (pinfunction "P$18_P$18") (pintype "bidirectional"))
      (node (ref "R12") (pin "P$2") (pinfunction "2_P$2") (pintype "passive"))
      (node (ref "U5") (pin "51") (pinfunction "P2_5_51") (pintype "bidirectional"))
    )
    (net (code "17") (name "IIC_SDA") (class "Default")
      (node (ref "J4") (pin "P$16") (pinfunction "P$16_P$16") (pintype "bidirectional"))
      (node (ref "R13") (pin "P$2") (pinfunction "2_P$2") (pintype "passive"))
      (node (ref "U5") (pin "50") (pinfunction "P2_6_50") (pintype "bidirectional"))
    )
    (net (code "18") (name "LS_4") (class "Default")
      (node (ref "J4") (pin "P$8") (pinfunction "P$8_P$8") (pintype "bidirectional"))
      (node (ref "U5") (pin "132") (pinfunction "P1_0_132") (pintype "bidirectional"))
    )
    (net (code "19") (name "LS_5") (class "Default")
      (node (ref "J4") (pin "P$10") (pinfunction "P$10_P$10") (pintype "bidirectional"))
      (node (ref "U5") (pin "131") (pinfunction "P1_1_131") (pintype "bidirectional"))
    )
    (net (code "20") (name "LS_6") (class "Default")
      (node (ref "J4") (pin "P$12") (pinfunction "P$12_P$12") (pintype "bidirectional"))
      (node (ref "U5") (pin "81") (pinfunction "P3_5_81") (pintype "bidirectional"))
    )
    (net (code "21") (name "M4_DIR") (class "Default")
      (node (ref "J4") (pin "P$7") (pinfunction "P$7_P$7") (pintype "bidirectional"))
      (node (ref "U5") (pin "101") (pinfunction "P6_10_101") (pintype "bidirectional"))
    )
    (net (code "22") (name "M4_STEP") (class "Default")
      (node (ref "J4") (pin "P$14") (pinfunction "P$14_P$14") (pintype "bidirectional"))
      (node (ref "U5") (pin "42") (pinfunction "P4_9_42") (pintype "bidirectional"))
    )
    (net (code "23") (name "Net-(C9-2)") (class "Default")
      (node (ref "C9") (pin "P$2") (pinfunction "2_P$2") (pintype "passive"))
      (node (ref "U5") (pin "148") (pinfunction "VCL2_148") (pintype "bidirectional"))
    )
    (net (code "24") (name "Net-(C16-1)") (class "Default")
      (node (ref "C16") (pin "P$1") (pinfunction "1_P$1") (pintype "passive"))
      (node (ref "J5") (pin "P$1") (pinfunction "VBUS_P$1") (pintype "bidirectional"))
      (node (ref "R4") (pin "P$2") (pinfunction "2_P$2") (pintype "passive"))
      (node (ref "R7") (pin "P$2") (pinfunction "2_P$2") (pintype "passive"))
    )
    (net (code "25") (name "Net-(C20-1)") (class "Default")
      (node (ref "C20") (pin "P$1") (pinfunction "1_P$1") (pintype "passive"))
      (node (ref "U5") (pin "19") (pinfunction "VCLO_19") (pintype "bidirectional"))
    )
    (net (code "26") (name "Net-(C28-1)") (class "Default")
      (node (ref "C28") (pin "P$1") (pinfunction "1_P$1") (pintype "passive"))
      (node (ref "U5") (pin "62") (pinfunction "VCL1_62") (pintype "bidirectional"))
    )
    (net (code "27") (name "Net-(J5-D+)") (class "Default")
      (node (ref "J5") (pin "P$3") (pinfunction "D+_P$3") (pintype "bidirectional"))
      (node (ref "R6") (pin "P$2") (pinfunction "2_P$2") (pintype "passive"))
    )
    (net (code "28") (name "Net-(J5-D-)") (class "Default")
      (node (ref "J5") (pin "P$2") (pinfunction "D-_P$2") (pintype "bidirectional"))
      (node (ref "R5") (pin "P$2") (pinfunction "2_P$2") (pintype "passive"))
    )
    (net (code "29") (name "Net-(R1-1)") (class "Default")
      (node (ref "LED1") (pin "A") (pinfunction "A_A") (pintype "passive"))
      (node (ref "R1") (pin "P$1") (pinfunction "1_P$1") (pintype "passive"))
    )
    (net (code "30") (name "Net-(R8-2)") (class "Default")
      (node (ref "R8") (pin "P$2") (pinfunction "2_P$2") (pintype "passive"))
      (node (ref "U5") (pin "64") (pinfunction "VLO1(DCDC)_64") (pintype "bidirectional"))
    )
    (net (code "31") (name "Net-(R9-2)") (class "Default")
      (node (ref "R9") (pin "P$2") (pinfunction "2_P$2") (pintype "passive"))
      (node (ref "U5") (pin "65") (pinfunction "VLO2(DCDC)_65") (pintype "bidirectional"))
    )
    (net (code "32") (name "Net-(R11-2)") (class "Default")
      (node (ref "R11") (pin "P$2") (pinfunction "2_P$2") (pintype "passive"))
      (node (ref "U5") (pin "27") (pinfunction "USBHS_RREF_27") (pintype "bidirectional"))
    )
    (net (code "33") (name "P1_02") (class "Default")
      (node (ref "U5") (pin "130") (pinfunction "P1_2_130") (pintype "bidirectional"))
    )
    (net (code "34") (name "P1_03") (class "Default")
      (node (ref "U5") (pin "129") (pinfunction "P1_3_129") (pintype "bidirectional"))
    )
    (net (code "35") (name "P1_04") (class "Default")
      (node (ref "U5") (pin "128") (pinfunction "P1_4_128") (pintype "bidirectional"))
    )
    (net (code "36") (name "P1_05") (class "Default")
      (node (ref "U5") (pin "127") (pinfunction "P1_5_127") (pintype "bidirectional"))
    )
    (net (code "37") (name "P1_06") (class "Default")
      (node (ref "U5") (pin "126") (pinfunction "P1_6_126") (pintype "bidirectional"))
    )
    (net (code "38") (name "P1_07") (class "Default")
      (node (ref "JP3") (pin "P$10") (pinfunction "P$10_P$10") (pintype "bidirectional"))
      (node (ref "U5") (pin "125") (pinfunction "P1_7_125") (pintype "bidirectional"))
    )
    (net (code "39") (name "P1_12") (class "Default")
      (node (ref "JP2") (pin "P$18") (pinfunction "P$18_P$18") (pintype "bidirectional"))
      (node (ref "U5") (pin "93") (pinfunction "P1_12_93") (pintype "bidirectional"))
    )
    (net (code "40") (name "P1_13") (class "Default")
      (node (ref "JP2") (pin "P$20") (pinfunction "P$20_P$20") (pintype "bidirectional"))
      (node (ref "U5") (pin "94") (pinfunction "P1_13_94") (pintype "bidirectional"))
    )
    (net (code "41") (name "P1_14") (class "Default")
      (node (ref "JP3") (pin "P$12") (pinfunction "P$12_P$12") (pintype "bidirectional"))
      (node (ref "U5") (pin "95") (pinfunction "P1_14_95") (pintype "bidirectional"))
    )
    (net (code "42") (name "P1_15") (class "Default")
      (node (ref "JP3") (pin "P$14") (pinfunction "P$14_P$14") (pintype "bidirectional"))
      (node (ref "U5") (pin "96") (pinfunction "P1_15_96") (pintype "bidirectional"))
    )
    (net (code "43") (name "P001_AN001") (class "Default")
      (node (ref "JP1") (pin "P$1") (pinfunction "P$1_P$1") (pintype "bidirectional"))
      (node (ref "U5") (pin "168") (pinfunction "P0_1/AN001_168") (pintype "bidirectional"))
    )
    (net (code "44") (name "P2_00") (class "Default")
      (node (ref "JP2") (pin "P$7") (pinfunction "P$7_P$7") (pintype "bidirectional"))
      (node (ref "U5") (pin "69") (pinfunction "P2_0(INPUT_ONLY)_69") (pintype "bidirectional"))
    )
    (net (code "45") (name "P2_07") (class "Default")
      (node (ref "JP2") (pin "P$19") (pinfunction "P$19_P$19") (pintype "bidirectional"))
      (node (ref "U5") (pin "49") (pinfunction "P2_7_49") (pintype "bidirectional"))
    )
    (net (code "46") (name "P002_AN002") (class "Default")
      (node (ref "JP1") (pin "P$3") (pinfunction "P$3_P$3") (pintype "bidirectional"))
      (node (ref "U5") (pin "167") (pinfunction "P0_2/AN002_167") (pintype "bidirectional"))
    )
    (net (code "47") (name "P003") (class "Default")
      (node (ref "JP1") (pin "P$5") (pinfunction "P$5_P$5") (pintype "bidirectional"))
      (node (ref "U5") (pin "166") (pinfunction "P0_3/PGAVSS000_166") (pintype "bidirectional"))
    )
    (net (code "48") (name "P3_01") (class "Default")
      (node (ref "U5") (pin "87") (pinfunction "P3_1_87") (pintype "bidirectional"))
    )
    (net (code "49") (name "P3_03") (class "Default")
      (node (ref "JP2") (pin "P$16") (pinfunction "P$16_P$16") (pintype "bidirectional"))
      (node (ref "U5") (pin "85") (pinfunction "P3_3_85") (pintype "bidirectional"))
    )
    (net (code "50") (name "P3_06") (class "Default")
      (node (ref "JP2") (pin "P$14") (pinfunction "P$14_P$14") (pintype "bidirectional"))
      (node (ref "U5") (pin "80") (pinfunction "P3_6_80") (pintype "bidirectional"))
    )
    (net (code "51") (name "P3_07") (class "Default")
      (node (ref "JP2") (pin "P$12") (pinfunction "P$12_P$12") (pintype "bidirectional"))
      (node (ref "U5") (pin "79") (pinfunction "P3_7_79") (pintype "bidirectional"))
    )
    (net (code "52") (name "P3_09") (class "Default")
      (node (ref "JP2") (pin "P$10") (pinfunction "P$10_P$10") (pintype "bidirectional"))
      (node (ref "U5") (pin "77") (pinfunction "P3_9_77") (pintype "bidirectional"))
    )
    (net (code "53") (name "P3_10") (class "Default")
      (node (ref "JP2") (pin "P$8") (pinfunction "P$8_P$8") (pintype "bidirectional"))
      (node (ref "U5") (pin "76") (pinfunction "P3_10_76") (pintype "bidirectional"))
    )
    (net (code "54") (name "P3_11") (class "Default")
      (node (ref "JP2") (pin "P$6") (pinfunction "P$6_P$6") (pintype "bidirectional"))
      (node (ref "U5") (pin "75") (pinfunction "P3_11_75") (pintype "bidirectional"))
    )
    (net (code "55") (name "P3_12") (class "Default")
      (node (ref "JP2") (pin "P$4") (pinfunction "P$4_P$4") (pintype "bidirectional"))
      (node (ref "U5") (pin "74") (pinfunction "P3_12_74") (pintype "bidirectional"))
    )
    (net (code "56") (name "P3_13") (class "Default")
      (node (ref "JP2") (pin "P$17") (pinfunction "P$17_P$17") (pintype "bidirectional"))
      (node (ref "U5") (pin "55") (pinfunction "P3_13_55") (pintype "bidirectional"))
    )
    (net (code "57") (name "P3_14") (class "Default")
      (node (ref "JP2") (pin "P$15") (pinfunction "P$15_P$15") (pintype "bidirectional"))
      (node (ref "U5") (pin "56") (pinfunction "P3_14_56") (pintype "bidirectional"))
    )
    (net (code "58") (name "P3_15") (class "Default")
      (node (ref "JP2") (pin "P$13") (pinfunction "P$13_P$13") (pintype "bidirectional"))
      (node (ref "U5") (pin "57") (pinfunction "P3_15_57") (pintype "bidirectional"))
    )
    (net (code "59") (name "P004_AN100") (class "Default")
      (node (ref "JP1") (pin "P$7") (pinfunction "P$7_P$7") (pintype "bidirectional"))
      (node (ref "U5") (pin "165") (pinfunction "P0_4/AN100_165") (pintype "bidirectional"))
    )
    (net (code "60") (name "P5_00_AN016") (class "Default")
      (node (ref "U5") (pin "140") (pinfunction "P5_0/AN016_140") (pintype "bidirectional"))
    )
    (net (code "61") (name "P5_01_AN116") (class "Default")
      (node (ref "JP1") (pin "P$8") (pinfunction "P$8_P$8") (pintype "bidirectional"))
      (node (ref "U5") (pin "141") (pinfunction "P5_1/AN116_141") (pintype "bidirectional"))
    )
    (net (code "62") (name "P5_02_AN017") (class "Default")
      (node (ref "JP1") (pin "P$10") (pinfunction "P$10_P$10") (pintype "bidirectional"))
      (node (ref "U5") (pin "142") (pinfunction "P5_2/AN017_142") (pintype "bidirectional"))
    )
    (net (code "63") (name "P5_03_AN117") (class "Default")
      (node (ref "JP1") (pin "P$12") (pinfunction "P$12_P$12") (pintype "bidirectional"))
      (node (ref "U5") (pin "143") (pinfunction "P5_3/AN117_143") (pintype "bidirectional"))
    )
    (net (code "64") (name "P5_04_AN018") (class "Default")
      (node (ref "JP1") (pin "P$14") (pinfunction "P$14_P$14") (pintype "bidirectional"))
      (node (ref "U5") (pin "144") (pinfunction "P5_4/AN018_144") (pintype "bidirectional"))
    )
    (net (code "65") (name "P5_05_AN118") (class "Default")
      (node (ref "JP1") (pin "P$16") (pinfunction "P$16_P$16") (pintype "bidirectional"))
      (node (ref "U5") (pin "145") (pinfunction "P5_5/AN118_145") (pintype "bidirectional"))
    )
    (net (code "66") (name "P5_06_AN019") (class "Default")
      (node (ref "JP1") (pin "P$18") (pinfunction "P$18_P$18") (pintype "bidirectional"))
      (node (ref "U5") (pin "146") (pinfunction "P5_6/AN019_146") (pintype "bidirectional"))
    )
    (net (code "67") (name "P5_07_AN119") (class "Default")
      (node (ref "JP1") (pin "P$20") (pinfunction "P$20_P$20") (pintype "bidirectional"))
      (node (ref "U5") (pin "147") (pinfunction "P5_7/AN119_147") (pintype "bidirectional"))
    )
    (net (code "68") (name "P5_11") (class "Default")
      (node (ref "JP1") (pin "P$6") (pinfunction "P$6_P$6") (pintype "bidirectional"))
      (node (ref "U5") (pin "176") (pinfunction "P5_11_176") (pintype "bidirectional"))
    )
    (net (code "69") (name "P5_13") (class "Default")
      (node (ref "JP1") (pin "P$4") (pinfunction "P$4_P$4") (pintype "bidirectional"))
      (node (ref "U5") (pin "174") (pinfunction "P5_13_174") (pintype "bidirectional"))
    )
    (net (code "70") (name "P6_00") (class "Default")
      (node (ref "JP3") (pin "P$8") (pinfunction "P$8_P$8") (pintype "bidirectional"))
      (node (ref "U5") (pin "122") (pinfunction "P6_0_122") (pintype "bidirectional"))
    )
    (net (code "71") (name "P6_02") (class "Default")
      (node (ref "JP3") (pin "P$6") (pinfunction "P$6_P$6") (pintype "bidirectional"))
      (node (ref "U5") (pin "120") (pinfunction "P6_2_120") (pintype "bidirectional"))
    )
    (net (code "72") (name "P6_03") (class "Default")
      (node (ref "JP3") (pin "P$4") (pinfunction "P$4_P$4") (pintype "bidirectional"))
      (node (ref "U5") (pin "119") (pinfunction "P6_3_119") (pintype "bidirectional"))
    )
    (net (code "73") (name "P6_05") (class "Default")
      (node (ref "JP3") (pin "P$2") (pinfunction "P$2_P$2") (pintype "bidirectional"))
      (node (ref "U5") (pin "117") (pinfunction "P6_5_117") (pintype "bidirectional"))
    )
    (net (code "74") (name "P6_06") (class "Default")
      (node (ref "JP3") (pin "P$1") (pinfunction "P$1_P$1") (pintype "bidirectional"))
      (node (ref "U5") (pin "116") (pinfunction "P6_6_116") (pintype "bidirectional"))
    )
    (net (code "75") (name "P6_08") (class "Default")
      (node (ref "JP3") (pin "P$16") (pinfunction "P$16_P$16") (pintype "bidirectional"))
      (node (ref "U5") (pin "99") (pinfunction "P6_8_99") (pintype "bidirectional"))
    )
    (net (code "76") (name "P6_09") (class "Default")
      (node (ref "JP3") (pin "P$18") (pinfunction "P$18_P$18") (pintype "bidirectional"))
      (node (ref "U5") (pin "100") (pinfunction "P6_9_100") (pintype "bidirectional"))
    )
    (net (code "77") (name "P6_11") (class "Default")
      (node (ref "JP3") (pin "P$20") (pinfunction "P$20_P$20") (pintype "bidirectional"))
      (node (ref "U5") (pin "102") (pinfunction "P6_11_102") (pintype "bidirectional"))
    )
    (net (code "78") (name "P6_12") (class "Default")
      (node (ref "JP3") (pin "P$19") (pinfunction "P$19_P$19") (pintype "bidirectional"))
      (node (ref "U5") (pin "103") (pinfunction "P6_12_103") (pintype "bidirectional"))
    )
    (net (code "79") (name "P6_13") (class "Default")
      (node (ref "JP3") (pin "P$17") (pinfunction "P$17_P$17") (pintype "bidirectional"))
      (node (ref "U5") (pin "104") (pinfunction "P6_13_104") (pintype "bidirectional"))
    )
    (net (code "80") (name "P6_14") (class "Default")
      (node (ref "JP3") (pin "P$15") (pinfunction "P$15_P$15") (pintype "bidirectional"))
      (node (ref "U5") (pin "105") (pinfunction "P6_14_105") (pintype "bidirectional"))
    )
    (net (code "81") (name "P6_15") (class "Default")
      (node (ref "JP3") (pin "P$13") (pinfunction "P$13_P$13") (pintype "bidirectional"))
      (node (ref "U5") (pin "106") (pinfunction "P6_15_106") (pintype "bidirectional"))
    )
    (net (code "82") (name "P006_AN102") (class "Default")
      (node (ref "JP1") (pin "P$9") (pinfunction "P$9_P$9") (pintype "bidirectional"))
      (node (ref "U5") (pin "163") (pinfunction "P0_6/AN102_163") (pintype "bidirectional"))
    )
    (net (code "83") (name "P007") (class "Default")
      (node (ref "JP1") (pin "P$11") (pinfunction "P$11_P$11") (pintype "bidirectional"))
      (node (ref "U5") (pin "162") (pinfunction "P0_7/PGVSS100_162") (pintype "bidirectional"))
    )
    (net (code "84") (name "P8_00") (class "Default")
      (node (ref "U5") (pin "133") (pinfunction "P8_0_133") (pintype "bidirectional"))
    )
    (net (code "85") (name "P8_01") (class "Default")
      (node (ref "U5") (pin "134") (pinfunction "P8_1_134") (pintype "bidirectional"))
    )
    (net (code "86") (name "P8_02") (class "Default")
      (node (ref "U5") (pin "135") (pinfunction "P8_2_135") (pintype "bidirectional"))
    )
    (net (code "87") (name "P8_03") (class "Default")
      (node (ref "U5") (pin "136") (pinfunction "P8_3_136") (pintype "bidirectional"))
    )
    (net (code "88") (name "P8_04") (class "Default")
      (node (ref "U5") (pin "137") (pinfunction "P8_4_137") (pintype "bidirectional"))
    )
    (net (code "89") (name "P8_05") (class "Default")
      (node (ref "JP1") (pin "P$2") (pinfunction "P$2_P$2") (pintype "bidirectional"))
      (node (ref "U5") (pin "173") (pinfunction "P8_5_173") (pintype "bidirectional"))
    )
    (net (code "90") (name "P008_AN003") (class "Default")
      (node (ref "JP1") (pin "P$13") (pinfunction "P$13_P$13") (pintype "bidirectional"))
      (node (ref "U5") (pin "161") (pinfunction "P0_8/AN003_161") (pintype "bidirectional"))
    )
    (net (code "91") (name "P9_00") (class "Default")
      (node (ref "JP2") (pin "P$11") (pinfunction "P$11_P$11") (pintype "bidirectional"))
      (node (ref "U5") (pin "58") (pinfunction "P9_0_58") (pintype "bidirectional"))
    )
    (net (code "92") (name "P9_01") (class "Default")
      (node (ref "JP2") (pin "P$9") (pinfunction "P$9_P$9") (pintype "bidirectional"))
      (node (ref "U5") (pin "59") (pinfunction "P9_1_59") (pintype "bidirectional"))
    )
    (net (code "93") (name "P9_05") (class "Default")
      (node (ref "JP2") (pin "P$2") (pinfunction "P$2_P$2") (pintype "bidirectional"))
      (node (ref "U5") (pin "73") (pinfunction "P9_5_73") (pintype "bidirectional"))
    )
    (net (code "94") (name "P9_06") (class "Default")
      (node (ref "JP2") (pin "P$1") (pinfunction "P$1_P$1") (pintype "bidirectional"))
      (node (ref "U5") (pin "72") (pinfunction "P9_6_72") (pintype "bidirectional"))
    )
    (net (code "95") (name "P9_07") (class "Default")
      (node (ref "JP2") (pin "P$3") (pinfunction "P$3_P$3") (pintype "bidirectional"))
      (node (ref "U5") (pin "71") (pinfunction "P9_7_71") (pintype "bidirectional"))
    )
    (net (code "96") (name "P9_08") (class "Default")
      (node (ref "JP2") (pin "P$5") (pinfunction "P$5_P$5") (pintype "bidirectional"))
      (node (ref "U5") (pin "70") (pinfunction "P9_8_70") (pintype "bidirectional"))
    )
    (net (code "97") (name "P009_AN004") (class "Default")
      (node (ref "JP1") (pin "P$15") (pinfunction "P$15_P$15") (pintype "bidirectional"))
      (node (ref "U5") (pin "160") (pinfunction "P0_9/AN004_160") (pintype "bidirectional"))
    )
    (net (code "98") (name "P014_DA0_AN005_AN105") (class "Default")
      (node (ref "JP1") (pin "P$17") (pinfunction "P$17_P$17") (pintype "bidirectional"))
      (node (ref "U5") (pin "152") (pinfunction "P0_14/DA0/AN005/AN105_152") (pintype "bidirectional"))
    )
    (net (code "99") (name "P015_DA1_AN006_AN106") (class "Default")
      (node (ref "JP1") (pin "P$19") (pinfunction "P$19_P$19") (pintype "bidirectional"))
      (node (ref "U5") (pin "151") (pinfunction "P0_15/DA1/AN006/AN106_151") (pintype "bidirectional"))
    )
    (net (code "100") (name "P400_ADC") (class "Default")
      (node (ref "U5") (pin "1") (pinfunction "P4_0_1") (pintype "bidirectional"))
    )
    (net (code "101") (name "PA_00") (class "Default")
      (node (ref "JP3") (pin "P$3") (pinfunction "P$3_P$3") (pintype "bidirectional"))
      (node (ref "U5") (pin "114") (pinfunction "PA_0_114") (pintype "bidirectional"))
    )
    (net (code "102") (name "PA_01") (class "Default")
      (node (ref "JP3") (pin "P$5") (pinfunction "P$5_P$5") (pintype "bidirectional"))
      (node (ref "U5") (pin "113") (pinfunction "PA_1_113") (pintype "bidirectional"))
    )
    (net (code "103") (name "PA_08") (class "Default")
      (node (ref "JP3") (pin "P$11") (pinfunction "P$11_P$11") (pintype "bidirectional"))
      (node (ref "U5") (pin "107") (pinfunction "PA_8_107") (pintype "bidirectional"))
    )
    (net (code "104") (name "PA_09") (class "Default")
      (node (ref "JP3") (pin "P$9") (pinfunction "P$9_P$9") (pintype "bidirectional"))
      (node (ref "U5") (pin "108") (pinfunction "PA_9_108") (pintype "bidirectional"))
    )
    (net (code "105") (name "PA_10") (class "Default")
      (node (ref "JP3") (pin "P$7") (pinfunction "P$7_P$7") (pintype "bidirectional"))
      (node (ref "U5") (pin "109") (pinfunction "PA_10_109") (pintype "bidirectional"))
    )
    (net (code "106") (name "RELAY_1") (class "Default")
      (node (ref "J4") (pin "P$15") (pinfunction "P$15_P$15") (pintype "bidirectional"))
      (node (ref "U5") (pin "68") (pinfunction "P2_1/MD_68") (pintype "bidirectional"))
    )
    (net (code "107") (name "RELAY_2") (class "Default")
      (node (ref "J4") (pin "P$17") (pinfunction "P$17_P$17") (pintype "bidirectional"))
      (node (ref "U5") (pin "54") (pinfunction "P2_2_54") (pintype "bidirectional"))
    )
    (net (code "108") (name "RELAY_3") (class "Default")
      (node (ref "J4") (pin "P$19") (pinfunction "P$19_P$19") (pintype "bidirectional"))
      (node (ref "U5") (pin "53") (pinfunction "P2_3_53") (pintype "bidirectional"))
    )
    (net (code "109") (name "RELAY_4") (class "Default")
      (node (ref "J4") (pin "P$20") (pinfunction "P$20_P$20") (pintype "bidirectional"))
      (node (ref "U5") (pin "52") (pinfunction "P2_4_52") (pintype "bidirectional"))
    )
    (net (code "110") (name "RESET") (class "Default")
      (node (ref "C29") (pin "P$1") (pinfunction "1_P$1") (pintype "passive"))
      (node (ref "J1") (pin "9") (pinfunction "9_9") (pintype "passive"))
      (node (ref "R10") (pin "P$1") (pinfunction "1_P$1") (pintype "passive"))
      (node (ref "U5") (pin "67") (pinfunction "RES#_67") (pintype "bidirectional"))
    )
    (net (code "111") (name "TCK") (class "Default")
      (node (ref "J1") (pin "7") (pinfunction "7_7") (pintype "passive"))
      (node (ref "U5") (pin "88") (pinfunction "P3_0_88") (pintype "bidirectional"))
    )
    (net (code "112") (name "TDI") (class "Default")
      (node (ref "J1") (pin "1") (pinfunction "1_1") (pintype "passive"))
      (node (ref "U5") (pin "91") (pinfunction "P1_10_91") (pintype "bidirectional"))
    )
    (net (code "113") (name "TDO") (class "Default")
      (node (ref "J1") (pin "3") (pinfunction "3_3") (pintype "passive"))
      (node (ref "U5") (pin "90") (pinfunction "P1_9_90") (pintype "bidirectional"))
    )
    (net (code "114") (name "TMS") (class "Default")
      (node (ref "J1") (pin "5") (pinfunction "5_5") (pintype "passive"))
      (node (ref "U5") (pin "89") (pinfunction "P1_8_89") (pintype "bidirectional"))
    )
    (net (code "115") (name "USBHS_FAULT") (class "Default")
      (node (ref "R2") (pin "P$1") (pinfunction "1_P$1") (pintype "passive"))
      (node (ref "U2") (pin "3") (pinfunction "FLG_3") (pintype "input"))
      (node (ref "U5") (pin "78") (pinfunction "P3_8_78") (pintype "bidirectional"))
    )
    (net (code "116") (name "USBHS_N") (class "Default")
      (node (ref "J2") (pin "D-") (pinfunction "D-_D-") (pintype "bidirectional"))
      (node (ref "U5") (pin "31") (pinfunction "USBHS_DM_31") (pintype "bidirectional"))
    )
    (net (code "117") (name "USBHS_P") (class "Default")
      (node (ref "J2") (pin "D+") (pinfunction "D+_D+") (pintype "bidirectional"))
      (node (ref "U5") (pin "32") (pinfunction "USBHS_DP_32") (pintype "bidirectional"))
    )
    (net (code "118") (name "USBHS_VBUS") (class "Default")
      (node (ref "C15") (pin "P$1") (pinfunction "1_P$1") (pintype "passive"))
      (node (ref "C18") (pin "1") (pinfunction "1_1") (pintype "passive"))
      (node (ref "J2") (pin "VBUS") (pinfunction "VBUS_VBUS") (pintype "power_in"))
      (node (ref "U2") (pin "5") (pinfunction "OUT_5") (pintype "input"))
      (node (ref "U5") (pin "17") (pinfunction "PB_1_17") (pintype "bidirectional"))
    )
    (net (code "119") (name "USBHS_VBUSEN") (class "Default")
      (node (ref "R3") (pin "P$1") (pinfunction "1_P$1") (pintype "passive"))
      (node (ref "U2") (pin "1") (pinfunction "EN_1") (pintype "input"))
      (node (ref "U5") (pin "16") (pinfunction "PB_0_16") (pintype "bidirectional"))
    )
    (net (code "120") (name "USB_N") (class "Default")
      (node (ref "R5") (pin "P$1") (pinfunction "1_P$1") (pintype "passive"))
      (node (ref "U5") (pin "46") (pinfunction "USB_DM_46") (pintype "bidirectional"))
    )
    (net (code "121") (name "USB_P") (class "Default")
      (node (ref "R6") (pin "P$1") (pinfunction "1_P$1") (pintype "passive"))
      (node (ref "U5") (pin "47") (pinfunction "USB_DP_47") (pintype "bidirectional"))
    )
    (net (code "122") (name "USB_VBUS_B") (class "Default")
      (node (ref "R4") (pin "P$1") (pinfunction "1_P$1") (pintype "passive"))
      (node (ref "U5") (pin "44") (pinfunction "P4_7_44") (pintype "bidirectional"))
    )
    (net (code "123") (name "VCL_F(FLASH)") (class "Default")
      (node (ref "C21") (pin "P$2") (pinfunction "2_P$2") (pintype "passive"))
      (node (ref "U5") (pin "112") (pinfunction "VCL_F(FLASH)_112") (pintype "bidirectional"))
    )
    (net (code "124") (name "VDD") (class "Default")
      (node (ref "C10") (pin "P$2") (pinfunction "2_P$2") (pintype "passive"))
      (node (ref "C12") (pin "P$2") (pinfunction "2_P$2") (pintype "passive"))
      (node (ref "C13") (pin "P$2") (pinfunction "2_P$2") (pintype "passive"))
      (node (ref "C17") (pin "P$2") (pinfunction "2_P$2") (pintype "passive"))
      (node (ref "C2") (pin "P$1") (pinfunction "1_P$1") (pintype "passive"))
      (node (ref "C22") (pin "P$2") (pinfunction "2_P$2") (pintype "passive"))
      (node (ref "C23") (pin "P$1") (pinfunction "1_P$1") (pintype "passive"))
      (node (ref "C25") (pin "P$2") (pinfunction "2_P$2") (pintype "passive"))
      (node (ref "C26") (pin "P$1") (pinfunction "1_P$1") (pintype "passive"))
      (node (ref "C27") (pin "P$1") (pinfunction "1_P$1") (pintype "passive"))
      (node (ref "C3") (pin "P$1") (pinfunction "1_P$1") (pintype "passive"))
      (node (ref "C30") (pin "P$1") (pinfunction "1_P$1") (pintype "passive"))
      (node (ref "C31") (pin "P$2") (pinfunction "2_P$2") (pintype "passive"))
      (node (ref "C4") (pin "P$1") (pinfunction "1_P$1") (pintype "passive"))
      (node (ref "C6") (pin "P$2") (pinfunction "2_P$2") (pintype "passive"))
      (node (ref "J1") (pin "2") (pinfunction "2_2") (pintype "passive"))
      (node (ref "J1") (pin "4") (pinfunction "4_4") (pintype "passive"))
      (node (ref "L1") (pin "2") (pinfunction "P$2_2") (pintype "bidirectional"))
      (node (ref "R1") (pin "P$2") (pinfunction "2_P$2") (pintype "passive"))
      (node (ref "R10") (pin "P$2") (pinfunction "2_P$2") (pintype "passive"))
      (node (ref "R12") (pin "P$1") (pinfunction "1_P$1") (pintype "passive"))
      (node (ref "R13") (pin "P$1") (pinfunction "1_P$1") (pintype "passive"))
      (node (ref "U1") (pin "P3") (pinfunction "VDD1_P3") (pintype "bidirectional"))
      (node (ref "U1") (pin "P4") (pinfunction "VDD_P4") (pintype "bidirectional"))
      (node (ref "U5") (pin "110") (pinfunction "VCC(IO)5_110") (pintype "bidirectional"))
      (node (ref "U5") (pin "123") (pinfunction "VCC(IO)6_123") (pintype "bidirectional"))
      (node (ref "U5") (pin "138") (pinfunction "VCC(IO)7_138") (pintype "bidirectional"))
      (node (ref "U5") (pin "149") (pinfunction "VCC(IO)8_149") (pintype "bidirectional"))
      (node (ref "U5") (pin "155") (pinfunction "AVCC0_155") (pintype "bidirectional"))
      (node (ref "U5") (pin "171") (pinfunction "VCC(IO)9_171") (pintype "bidirectional"))
      (node (ref "U5") (pin "25") (pinfunction "VCC1_25") (pintype "bidirectional"))
      (node (ref "U5") (pin "26") (pinfunction "AVCC_SUBHS_26") (pintype "bidirectional"))
      (node (ref "U5") (pin "34") (pinfunction "VCC_USBHS_34") (pintype "bidirectional"))
      (node (ref "U5") (pin "48") (pinfunction "VCC_USB_48") (pintype "bidirectional"))
      (node (ref "U5") (pin "61") (pinfunction "VCC(IO)2_61") (pintype "bidirectional"))
      (node (ref "U5") (pin "84") (pinfunction "VCC(IO)3_84") (pintype "bidirectional"))
      (node (ref "U5") (pin "97") (pinfunction "VCC(IO)4_97") (pintype "bidirectional"))
    )
    (net (code "125") (name "VDD5") (class "Default")
      (node (ref "C11") (pin "P$1") (pinfunction "1_P$1") (pintype "passive"))
      (node (ref "C8") (pin "P$1") (pinfunction "1_P$1") (pintype "passive"))
      (node (ref "J3") (pin "P$3") (pinfunction "P$3_P$3") (pintype "bidirectional"))
      (node (ref "R2") (pin "P$2") (pinfunction "2_P$2") (pintype "passive"))
      (node (ref "R3") (pin "P$2") (pinfunction "2_P$2") (pintype "passive"))
      (node (ref "U2") (pin "4") (pinfunction "VIN_4") (pintype "input"))
    )
    (net (code "126") (name "VDDIN") (class "Default")
      (node (ref "J3") (pin "P$2") (pinfunction "P$2_P$2") (pintype "bidirectional"))
      (node (ref "L1") (pin "1") (pinfunction "P$1_1") (pintype "bidirectional"))
    )
    (net (code "127") (name "XCIN") (class "Default")
      (node (ref "C19") (pin "P$1") (pinfunction "1_P$1") (pintype "passive"))
      (node (ref "U5") (pin "20") (pinfunction "XCIN_20") (pintype "bidirectional"))
      (node (ref "X2") (pin "P$1") (pinfunction "P$1_P$1") (pintype "bidirectional"))
    )
    (net (code "128") (name "XCOUT") (class "Default")
      (node (ref "C24") (pin "P$1") (pinfunction "1_P$1") (pintype "passive"))
      (node (ref "U5") (pin "21") (pinfunction "XCOUT_21") (pintype "bidirectional"))
      (node (ref "X2") (pin "P$2") (pinfunction "P$2_P$2") (pintype "bidirectional"))
    )
    (net (code "129") (name "XTAL1") (class "Default")
      (node (ref "C7") (pin "P$1") (pinfunction "1_P$1") (pintype "passive"))
      (node (ref "U5") (pin "23") (pinfunction "P2_13/XTAL_23") (pintype "bidirectional"))
      (node (ref "X1") (pin "1") (pinfunction "1_1") (pintype "bidirectional"))
    )
    (net (code "130") (name "XTAL2") (class "Default")
      (node (ref "C14") (pin "P$1") (pinfunction "1_P$1") (pintype "passive"))
      (node (ref "U5") (pin "24") (pinfunction "P2_12/EXTAL_24") (pintype "bidirectional"))
      (node (ref "X1") (pin "3") (pinfunction "3_3") (pintype "bidirectional"))
    )
    (net (code "131") (name "X_DIR") (class "Default")
      (node (ref "J4") (pin "P$3") (pinfunction "P$3_P$3") (pintype "bidirectional"))
      (node (ref "U5") (pin "118") (pinfunction "P6_4_118") (pintype "bidirectional"))
    )
    (net (code "132") (name "X_LS") (class "Default")
      (node (ref "J4") (pin "P$2") (pinfunction "P$2_P$2") (pintype "bidirectional"))
      (node (ref "U5") (pin "164") (pinfunction "P0_5/AN101_164") (pintype "bidirectional"))
    )
    (net (code "133") (name "X_STEP") (class "Default")
      (node (ref "J4") (pin "P$11") (pinfunction "P$11_P$11") (pintype "bidirectional"))
      (node (ref "U5") (pin "86") (pinfunction "P3_2_86") (pintype "bidirectional"))
    )
    (net (code "134") (name "Y_DIR") (class "Default")
      (node (ref "J4") (pin "P$5") (pinfunction "P$5_P$5") (pintype "bidirectional"))
      (node (ref "U5") (pin "115") (pinfunction "P6_7_115") (pintype "bidirectional"))
    )
    (net (code "135") (name "Y_LS") (class "Default")
      (node (ref "J4") (pin "P$4") (pinfunction "P$4_P$4") (pintype "bidirectional"))
      (node (ref "U5") (pin "175") (pinfunction "P5_12_175") (pintype "bidirectional"))
    )
    (net (code "136") (name "Y_STEP") (class "Default")
      (node (ref "J4") (pin "P$13") (pinfunction "P$13_P$13") (pintype "bidirectional"))
      (node (ref "U5") (pin "82") (pinfunction "P3_4_82") (pintype "bidirectional"))
    )
    (net (code "137") (name "Z_DIR") (class "Default")
      (node (ref "J4") (pin "P$1") (pinfunction "P$1_P$1") (pintype "bidirectional"))
      (node (ref "U5") (pin "121") (pinfunction "P6_1_121") (pintype "bidirectional"))
    )
    (net (code "138") (name "Z_LS") (class "Default")
      (node (ref "J4") (pin "P$6") (pinfunction "P$6_P$6") (pintype "bidirectional"))
      (node (ref "U5") (pin "169") (pinfunction "P0_0/AN0\\00_169") (pintype "bidirectional"))
    )
    (net (code "139") (name "Z_STEP") (class "Default")
      (node (ref "J4") (pin "P$9") (pinfunction "P$9_P$9") (pintype "bidirectional"))
      (node (ref "U5") (pin "92") (pinfunction "P1_11_92") (pintype "bidirectional"))
    )
    (net (code "140") (name "unconnected-(U5-P4_1-Pad2)") (class "Default")
      (node (ref "U5") (pin "2") (pinfunction "P4_1_2") (pintype "bidirectional"))
    )
    (net (code "141") (name "unconnected-(U5-P4_2-Pad3)") (class "Default")
      (node (ref "U5") (pin "3") (pinfunction "P4_2_3") (pintype "bidirectional"))
    )
    (net (code "142") (name "unconnected-(U5-P4_8-Pad43)") (class "Default")
      (node (ref "U5") (pin "43") (pinfunction "P4_8_43") (pintype "bidirectional"))
    )
    (net (code "143") (name "unconnected-(U5-P4_10-Pad41)") (class "Default")
      (node (ref "U5") (pin "41") (pinfunction "P4_10_41") (pintype "bidirectional"))
    )
    (net (code "144") (name "unconnected-(U5-P4_11-Pad40)") (class "Default")
      (node (ref "U5") (pin "40") (pinfunction "P4_11_40") (pintype "bidirectional"))
    )
    (net (code "145") (name "unconnected-(U5-P4_12-Pad39)") (class "Default")
      (node (ref "U5") (pin "39") (pinfunction "P4_12_39") (pintype "bidirectional"))
    )
    (net (code "146") (name "unconnected-(U5-P4_13-Pad38)") (class "Default")
      (node (ref "U5") (pin "38") (pinfunction "P4_13_38") (pintype "bidirectional"))
    )
    (net (code "147") (name "unconnected-(U5-P4_14-Pad37)") (class "Default")
      (node (ref "U5") (pin "37") (pinfunction "P4_14_37") (pintype "bidirectional"))
    )
    (net (code "148") (name "unconnected-(U5-P4_15-Pad36)") (class "Default")
      (node (ref "U5") (pin "36") (pinfunction "P4_15_36") (pintype "bidirectional"))
    )
    (net (code "149") (name "unconnected-(U5-P7_6-Pad14)") (class "Default")
      (node (ref "U5") (pin "14") (pinfunction "P7_6_14") (pintype "bidirectional"))
    )
    (net (code "150") (name "unconnected-(U5-P7_7-Pad15)") (class "Default")
      (node (ref "U5") (pin "15") (pinfunction "P7_7_15") (pintype "bidirectional"))
    )
    (net (code "151") (name "unconnected-(U5-VBAT-Pad18)") (class "Default")
      (node (ref "U5") (pin "18") (pinfunction "VBAT_18") (pintype "bidirectional"))
    )
    (net (code "152") (name "unconnected-(U5-VREFH-Pad154)") (class "Default")
      (node (ref "U5") (pin "154") (pinfunction "VREFH_154") (pintype "bidirectional"))
    )
    (net (code "153") (name "unconnected-(U5-VREFH0-Pad158)") (class "Default")
      (node (ref "U5") (pin "158") (pinfunction "VREFH0_158") (pintype "bidirectional"))
    )
    (net (code "154") (name "unconnected-(U5-VREFL-Pad153)") (class "Default")
      (node (ref "U5") (pin "153") (pinfunction "VREFL_153") (pintype "bidirectional"))
    )
    (net (code "155") (name "unconnected-(U5-VREFL0-Pad157)") (class "Default")
      (node (ref "U5") (pin "157") (pinfunction "VREFL0_157") (pintype "bidirectional"))
    )
  )
)
